# EEM_connector.net
KiCad netlist of a schematic drawn in Altium Designer
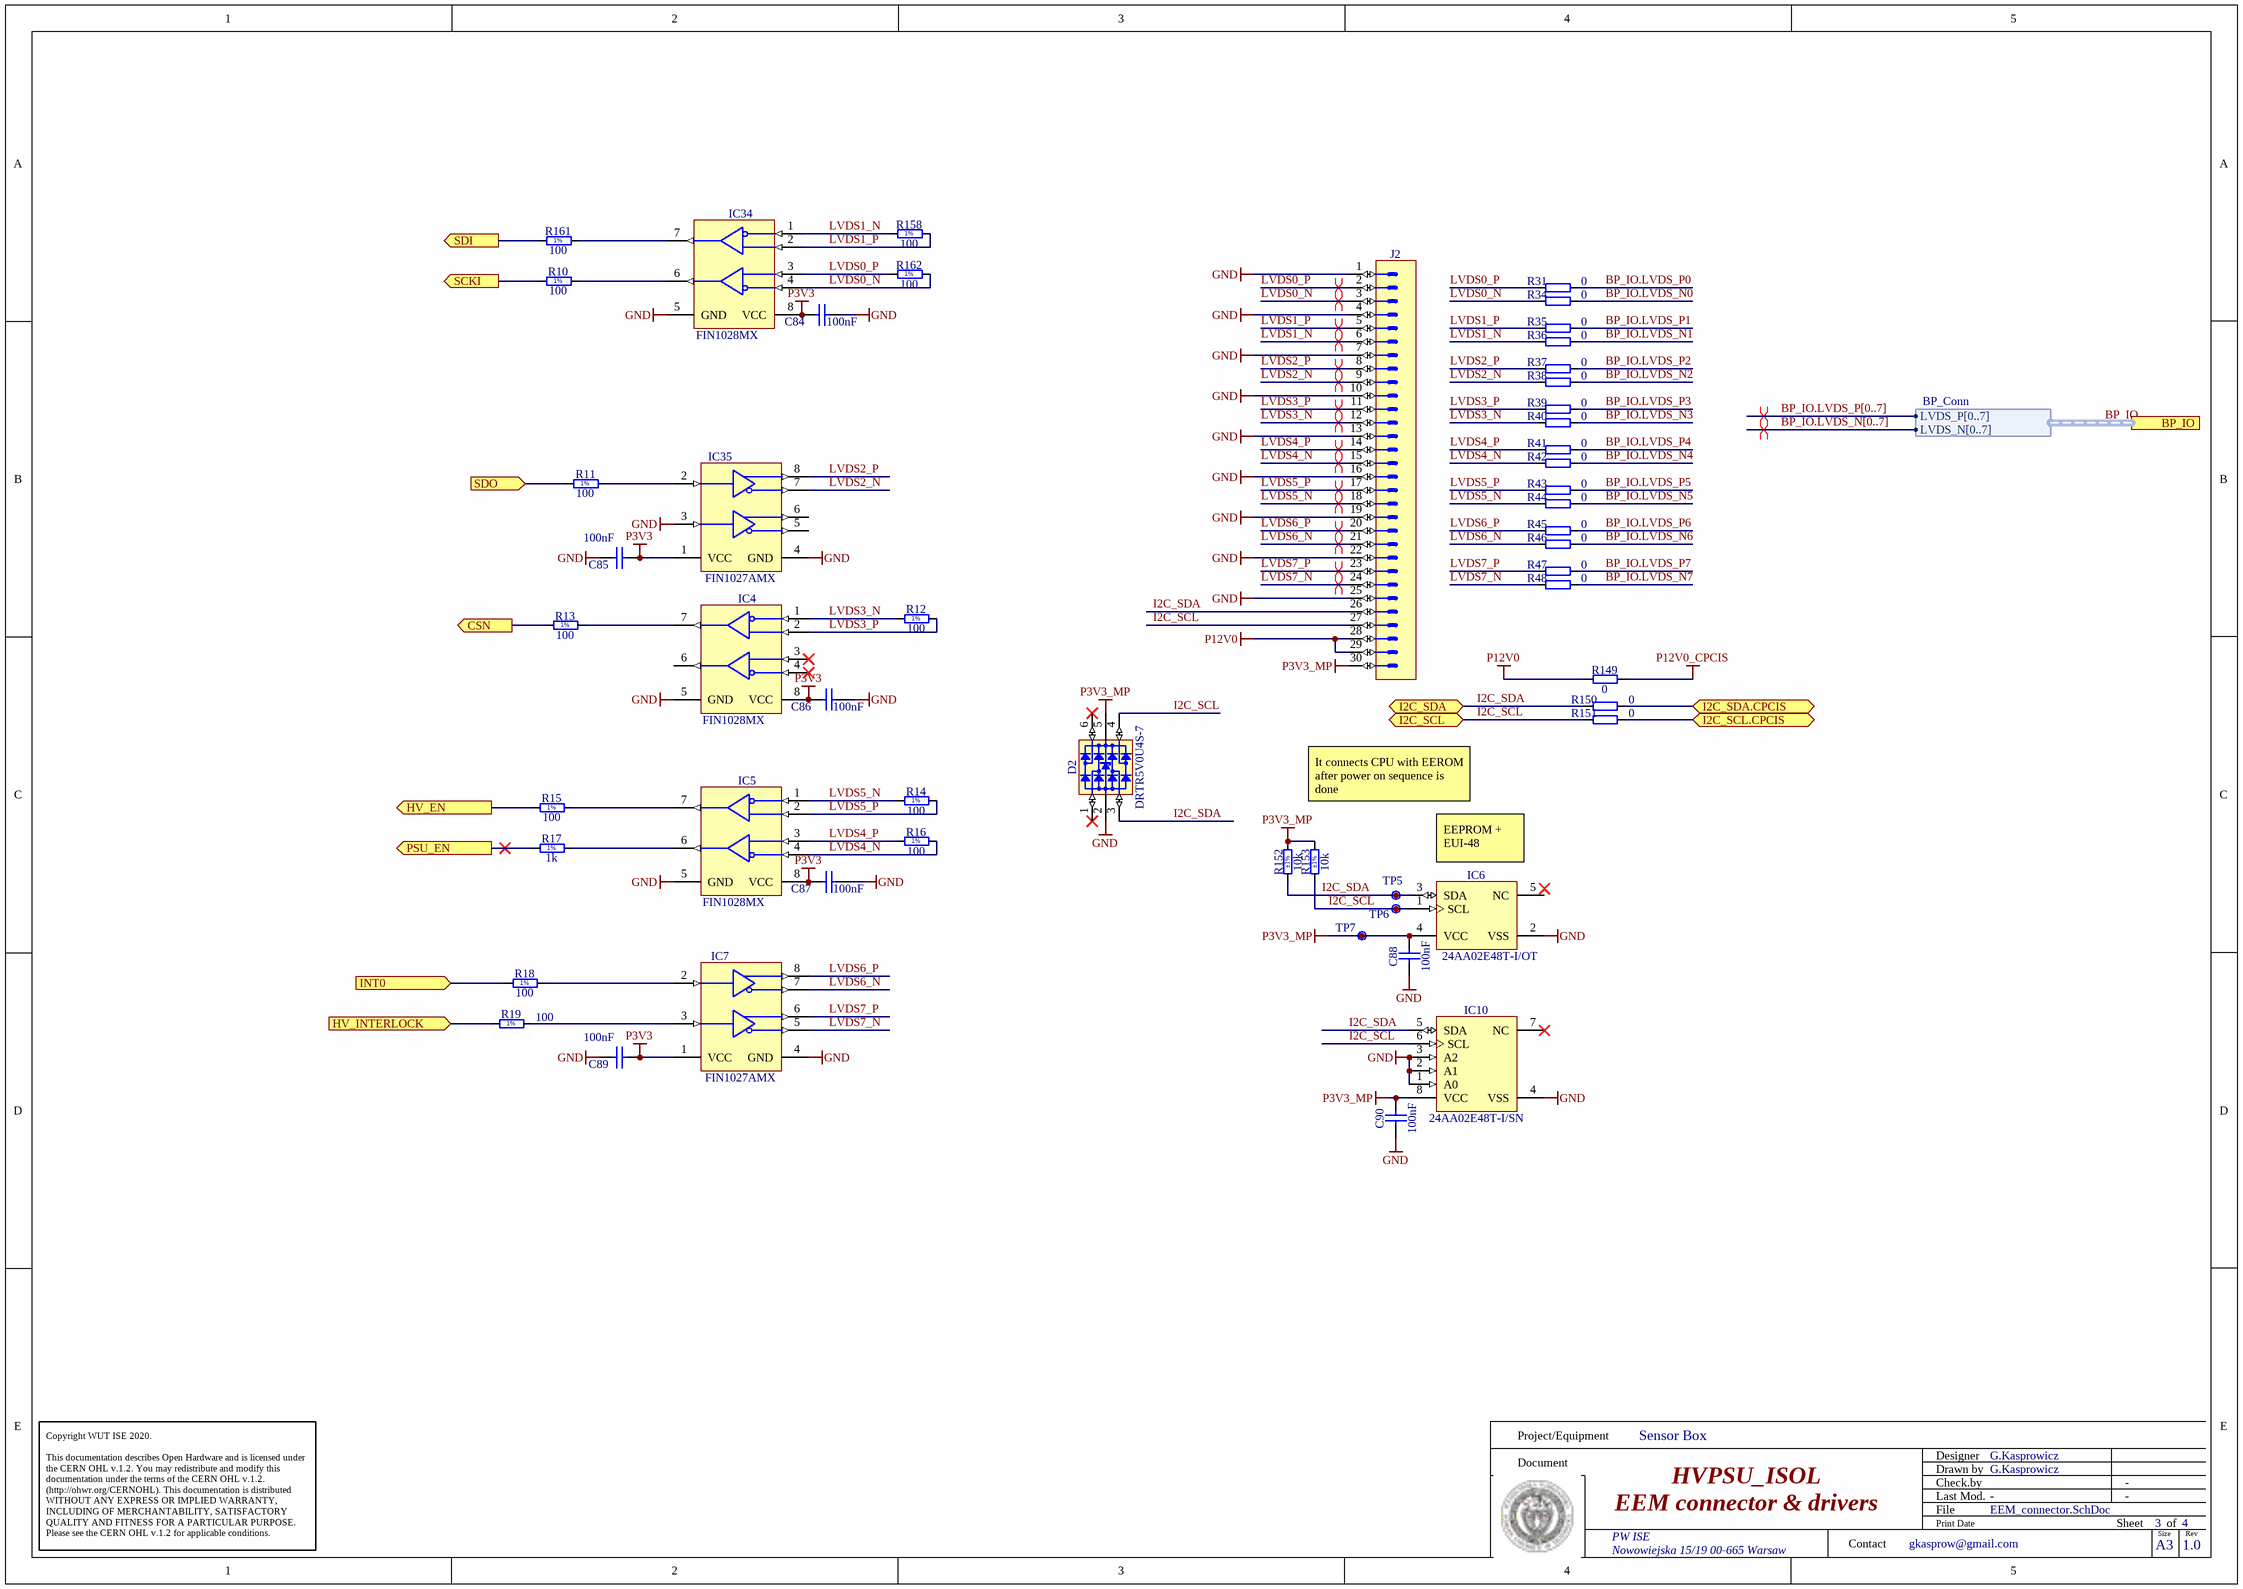
[diagram p0: EEM_connector.SchDoc]

(export (version "E")
  (design (tool "Eeschema 10.0.6"))
  (components
    (comp (ref "C84")
      (value "100nF")
      (footprint "CAPC1005X55N")
      (description "Non-polarised capacitor")
      (fields
        (field (name "PART NUMBER") "CC0402_100NF_16V_10%_X5R")
        (field (name "VOLTAGE") "16V")
        (field (name "AUTHOR") "CERN DEM JLC")
      )
      (libsource (lib "Capacitors") (part "Capacitor - non polarized"))
    )
    (comp (ref "C85")
      (value "100nF")
      (footprint "CAPC1005X55N")
      (description "Non-polarised capacitor")
      (fields
        (field (name "PART NUMBER") "CC0402_100NF_16V_10%_X5R")
        (field (name "VOLTAGE") "16V")
        (field (name "AUTHOR") "CERN DEM JLC")
      )
      (libsource (lib "Capacitors") (part "Capacitor - non polarized"))
    )
    (comp (ref "C86")
      (value "100nF")
      (footprint "CAPC1005X55N")
      (description "Non-polarised capacitor")
      (fields
        (field (name "PART NUMBER") "CC0402_100NF_16V_10%_X5R")
        (field (name "VOLTAGE") "16V")
        (field (name "AUTHOR") "CERN DEM JLC")
      )
      (libsource (lib "Capacitors") (part "Capacitor - non polarized"))
    )
    (comp (ref "C87")
      (value "100nF")
      (footprint "CAPC1005X55N")
      (description "Non-polarised capacitor")
      (fields
        (field (name "PART NUMBER") "CC0402_100NF_16V_10%_X5R")
        (field (name "VOLTAGE") "16V")
        (field (name "AUTHOR") "CERN DEM JLC")
      )
      (libsource (lib "Capacitors") (part "Capacitor - non polarized"))
    )
    (comp (ref "C88")
      (value "100nF")
      (footprint "CAPC1005X55N")
      (description "Non-polarised capacitor")
      (fields
        (field (name "PART NUMBER") "CC0402_100NF_16V_10%_X5R")
        (field (name "VOLTAGE") "16V")
        (field (name "AUTHOR") "CERN DEM JLC")
      )
      (libsource (lib "Capacitors") (part "Capacitor - non polarized"))
    )
    (comp (ref "C89")
      (value "100nF")
      (footprint "CAPC1005X55N")
      (description "Non-polarised capacitor")
      (fields
        (field (name "PART NUMBER") "CC0402_100NF_16V_10%_X5R")
        (field (name "VOLTAGE") "16V")
        (field (name "AUTHOR") "CERN DEM JLC")
      )
      (libsource (lib "Capacitors") (part "Capacitor - non polarized"))
    )
    (comp (ref "C90")
      (value "100nF")
      (footprint "CAPC1005X55N")
      (description "Non-polarised capacitor")
      (fields
        (field (name "PART NUMBER") "CC0402_100NF_16V_10%_X5R")
        (field (name "VOLTAGE") "16V")
        (field (name "AUTHOR") "CERN DEM JLC")
      )
      (libsource (lib "Capacitors") (part "Capacitor - non polarized"))
    )
    (comp (ref "D2")
      (value "DRTR5V0U4S-7")
      (footprint "SOT65P210X110-6N")
      (description "Integrated Quad Ultra-Low Capacitance ESD Protection")
      (fields (field (name "MANUFACTURER") "DIODES") (field (name "AUTHOR") "GK"))
      (libsource (lib "Diodes") (part "D_TVS_DRTR5V0U4S-7"))
    )
    (comp (ref "IC4")
      (value "FIN1028MX")
      (footprint "SOIC127P600X175-8N")
      (description "3.3V LVDS 2-Bit High-Speed Differential Reciever")
      (fields (field (name "MANUFACTURER") "ON Semiconductor") (field (name "AUTHOR") "GK"))
      (libsource (lib "LIBRARY_SCH") (part "IFC_FIN1028"))
    )
    (comp (ref "IC5")
      (value "FIN1028MX")
      (footprint "SOIC127P600X175-8N")
      (description "3.3V LVDS 2-Bit High-Speed Differential Reciever")
      (fields (field (name "MANUFACTURER") "ON Semiconductor") (field (name "AUTHOR") "GK"))
      (libsource (lib "LIBRARY_SCH") (part "IFC_FIN1028"))
    )
    (comp (ref "IC6")
      (value "24AA02E48T-I/OT")
      (footprint "SOT95P280X145-5N")
      (description "1.7V-5.5V, 2K I2C Serial EEPROM With EUI-48 Node Identity")
      (fields (field (name "MANUFACTURER") "MICROCHIP TECHNOLOGY") (field (name "AUTHOR") "CERN DEM MR"))
      (libsource (lib "ICs And Semiconductors") (part "24AA02E48T-I/OT"))
    )
    (comp (ref "IC7")
      (value "FIN1027AMX")
      (footprint "SOIC127P600X175-8N")
      (description "3.3V LVDS, 2-Bit, High-Speed, Differential Driver")
      (fields (field (name "MANUFACTURER") "ON Semiconductor") (field (name "AUTHOR") "GK"))
      (libsource (lib "LIBRARY_SCH") (part "IFC_FIN1027A"))
    )
    (comp (ref "IC10")
      (value "24AA02E48T-I/SN")
      (footprint "SOIC127P600X175-8N")
      (description "1.7V-5.5V, 2K I2C™ Serial EEPROMs with EUI-48™ Node Identity")
      (fields (field (name "MANUFACTURER") "MICROCHIP TECHNOLOGY") (field (name "AUTHOR") "CERN DEM MR"))
      (libsource (lib "ICs And Semiconductors") (part "24AA025E48-I/SN"))
    )
    (comp (ref "IC34")
      (value "FIN1028MX")
      (footprint "SOIC127P600X175-8N")
      (description "3.3V LVDS 2-Bit High-Speed Differential Reciever")
      (fields (field (name "MANUFACTURER") "ON Semiconductor") (field (name "AUTHOR") "GK"))
      (libsource (lib "LIBRARY_SCH") (part "IFC_FIN1028"))
    )
    (comp (ref "IC35")
      (value "FIN1027AMX")
      (footprint "SOIC127P600X175-8N")
      (description "3.3V LVDS, 2-Bit, High-Speed, Differential Driver")
      (fields (field (name "MANUFACTURER") "ON Semiconductor") (field (name "AUTHOR") "GK"))
      (libsource (lib "LIBRARY_SCH") (part "IFC_FIN1027A"))
    )
    (comp (ref "J2")
      (value "IDC")
      (footprint "3M_N2530-6002RB")
      (description "Connector 30 Male")
      (fields
        (field (name "PART NUMBER") "3M_N2530-6002RB")
        (field (name "MANUFACTURER") "3M")
        (field (name "AUTHOR") "CERN DEM JLC")
      )
      (libsource (lib "Connectors") (part "Connector 30 Male"))
    )
    (comp (ref "R10")
      (value "100")
      (footprint "RESC1005X40N")
      (description "Resistor - 1%")
      (fields
        (field (name "PART NUMBER") "R0402_100R_1%_0.0625W_100PPM")
        (field (name "POWER") "0.0625W")
        (field (name "AUTHOR") "CERN DEM JLC")
      )
      (libsource (lib "Resistors") (part "Resistor - 1%"))
    )
    (comp (ref "R11")
      (value "100")
      (footprint "RESC1005X40N")
      (description "Resistor - 1%")
      (fields
        (field (name "PART NUMBER") "R0402_100R_1%_0.0625W_100PPM")
        (field (name "POWER") "0.0625W")
        (field (name "AUTHOR") "CERN DEM JLC")
      )
      (libsource (lib "Resistors") (part "Resistor - 1%"))
    )
    (comp (ref "R12")
      (value "100")
      (footprint "RESC1005X40N")
      (description "Resistor - 1%")
      (fields
        (field (name "PART NUMBER") "R0402_100R_1%_0.0625W_100PPM")
        (field (name "POWER") "0.0625W")
        (field (name "AUTHOR") "CERN DEM JLC")
      )
      (libsource (lib "Resistors") (part "Resistor - 1%"))
    )
    (comp (ref "R13")
      (value "100")
      (footprint "RESC1005X40N")
      (description "Resistor - 1%")
      (fields
        (field (name "PART NUMBER") "R0402_100R_1%_0.0625W_100PPM")
        (field (name "POWER") "0.0625W")
        (field (name "AUTHOR") "CERN DEM JLC")
      )
      (libsource (lib "Resistors") (part "Resistor - 1%"))
    )
    (comp (ref "R14")
      (value "100")
      (footprint "RESC1005X40N")
      (description "Resistor - 1%")
      (fields
        (field (name "PART NUMBER") "R0402_100R_1%_0.0625W_100PPM")
        (field (name "POWER") "0.0625W")
        (field (name "AUTHOR") "CERN DEM JLC")
      )
      (libsource (lib "Resistors") (part "Resistor - 1%"))
    )
    (comp (ref "R15")
      (value "100")
      (footprint "RESC1005X40N")
      (description "Resistor - 1%")
      (fields
        (field (name "PART NUMBER") "R0402_100R_1%_0.0625W_100PPM")
        (field (name "POWER") "0.0625W")
        (field (name "AUTHOR") "CERN DEM JLC")
      )
      (libsource (lib "Resistors") (part "Resistor - 1%"))
    )
    (comp (ref "R16")
      (value "100")
      (footprint "RESC1005X40N")
      (description "Resistor - 1%")
      (fields
        (field (name "PART NUMBER") "R0402_100R_1%_0.0625W_100PPM")
        (field (name "POWER") "0.0625W")
        (field (name "AUTHOR") "CERN DEM JLC")
      )
      (libsource (lib "Resistors") (part "Resistor - 1%"))
    )
    (comp (ref "R17")
      (value "1k")
      (footprint "RESC1005X40N")
      (description "Resistor - 1%")
      (fields
        (field (name "PART NUMBER") "R0402_1K_1%_0.0625W_100PPM")
        (field (name "POWER") "0.0625W")
        (field (name "AUTHOR") "CERN DEM JLC")
      )
      (libsource (lib "Resistors") (part "Resistor - 1%"))
    )
    (comp (ref "R18")
      (value "100")
      (footprint "RESC1005X40N")
      (description "Resistor - 1%")
      (fields
        (field (name "PART NUMBER") "R0402_100R_1%_0.0625W_100PPM")
        (field (name "POWER") "0.0625W")
        (field (name "AUTHOR") "CERN DEM JLC")
      )
      (libsource (lib "Resistors") (part "Resistor - 1%"))
    )
    (comp (ref "R19")
      (value "100")
      (footprint "RESC1005X40N")
      (description "Resistor - 1%")
      (fields
        (field (name "PART NUMBER") "R0402_100R_1%_0.0625W_100PPM")
        (field (name "POWER") "0.0625W")
        (field (name "AUTHOR") "CERN DEM JLC")
      )
      (libsource (lib "Resistors") (part "Resistor - 1%"))
    )
    (comp (ref "R31")
      (value "0")
      (footprint "RESC1005X40N")
      (description "Resistor")
      (fields
        (field (name "PART NUMBER") "R0402_0R_JUMPER")
        (field (name "MANUFACTURER") "GENERIC")
        (field (name "AUTHOR") "CERN DEM JLC")
      )
      (libsource (lib "Resistors") (part "Resistor"))
    )
    (comp (ref "R34")
      (value "0")
      (footprint "RESC1005X40N")
      (description "Resistor")
      (fields
        (field (name "PART NUMBER") "R0402_0R_JUMPER")
        (field (name "MANUFACTURER") "GENERIC")
        (field (name "AUTHOR") "CERN DEM JLC")
      )
      (libsource (lib "Resistors") (part "Resistor"))
    )
    (comp (ref "R35")
      (value "0")
      (footprint "RESC1005X40N")
      (description "Resistor")
      (fields
        (field (name "PART NUMBER") "R0402_0R_JUMPER")
        (field (name "MANUFACTURER") "GENERIC")
        (field (name "AUTHOR") "CERN DEM JLC")
      )
      (libsource (lib "Resistors") (part "Resistor"))
    )
    (comp (ref "R36")
      (value "0")
      (footprint "RESC1005X40N")
      (description "Resistor")
      (fields
        (field (name "PART NUMBER") "R0402_0R_JUMPER")
        (field (name "MANUFACTURER") "GENERIC")
        (field (name "AUTHOR") "CERN DEM JLC")
      )
      (libsource (lib "Resistors") (part "Resistor"))
    )
    (comp (ref "R37")
      (value "0")
      (footprint "RESC1005X40N")
      (description "Resistor")
      (fields
        (field (name "PART NUMBER") "R0402_0R_JUMPER")
        (field (name "MANUFACTURER") "GENERIC")
        (field (name "AUTHOR") "CERN DEM JLC")
      )
      (libsource (lib "Resistors") (part "Resistor"))
    )
    (comp (ref "R38")
      (value "0")
      (footprint "RESC1005X40N")
      (description "Resistor")
      (fields
        (field (name "PART NUMBER") "R0402_0R_JUMPER")
        (field (name "MANUFACTURER") "GENERIC")
        (field (name "AUTHOR") "CERN DEM JLC")
      )
      (libsource (lib "Resistors") (part "Resistor"))
    )
    (comp (ref "R39")
      (value "0")
      (footprint "RESC1005X40N")
      (description "Resistor")
      (fields
        (field (name "PART NUMBER") "R0402_0R_JUMPER")
        (field (name "MANUFACTURER") "GENERIC")
        (field (name "AUTHOR") "CERN DEM JLC")
      )
      (libsource (lib "Resistors") (part "Resistor"))
    )
    (comp (ref "R40")
      (value "0")
      (footprint "RESC1005X40N")
      (description "Resistor")
      (fields
        (field (name "PART NUMBER") "R0402_0R_JUMPER")
        (field (name "MANUFACTURER") "GENERIC")
        (field (name "AUTHOR") "CERN DEM JLC")
      )
      (libsource (lib "Resistors") (part "Resistor"))
    )
    (comp (ref "R41")
      (value "0")
      (footprint "RESC1005X40N")
      (description "Resistor")
      (fields
        (field (name "PART NUMBER") "R0402_0R_JUMPER")
        (field (name "MANUFACTURER") "GENERIC")
        (field (name "AUTHOR") "CERN DEM JLC")
      )
      (libsource (lib "Resistors") (part "Resistor"))
    )
    (comp (ref "R42")
      (value "0")
      (footprint "RESC1005X40N")
      (description "Resistor")
      (fields
        (field (name "PART NUMBER") "R0402_0R_JUMPER")
        (field (name "MANUFACTURER") "GENERIC")
        (field (name "AUTHOR") "CERN DEM JLC")
      )
      (libsource (lib "Resistors") (part "Resistor"))
    )
    (comp (ref "R43")
      (value "0")
      (footprint "RESC1005X40N")
      (description "Resistor")
      (fields
        (field (name "PART NUMBER") "R0402_0R_JUMPER")
        (field (name "MANUFACTURER") "GENERIC")
        (field (name "AUTHOR") "CERN DEM JLC")
      )
      (libsource (lib "Resistors") (part "Resistor"))
    )
    (comp (ref "R44")
      (value "0")
      (footprint "RESC1005X40N")
      (description "Resistor")
      (fields
        (field (name "PART NUMBER") "R0402_0R_JUMPER")
        (field (name "MANUFACTURER") "GENERIC")
        (field (name "AUTHOR") "CERN DEM JLC")
      )
      (libsource (lib "Resistors") (part "Resistor"))
    )
    (comp (ref "R45")
      (value "0")
      (footprint "RESC1005X40N")
      (description "Resistor")
      (fields
        (field (name "PART NUMBER") "R0402_0R_JUMPER")
        (field (name "MANUFACTURER") "GENERIC")
        (field (name "AUTHOR") "CERN DEM JLC")
      )
      (libsource (lib "Resistors") (part "Resistor"))
    )
    (comp (ref "R46")
      (value "0")
      (footprint "RESC1005X40N")
      (description "Resistor")
      (fields
        (field (name "PART NUMBER") "R0402_0R_JUMPER")
        (field (name "MANUFACTURER") "GENERIC")
        (field (name "AUTHOR") "CERN DEM JLC")
      )
      (libsource (lib "Resistors") (part "Resistor"))
    )
    (comp (ref "R47")
      (value "0")
      (footprint "RESC1005X40N")
      (description "Resistor")
      (fields
        (field (name "PART NUMBER") "R0402_0R_JUMPER")
        (field (name "MANUFACTURER") "GENERIC")
        (field (name "AUTHOR") "CERN DEM JLC")
      )
      (libsource (lib "Resistors") (part "Resistor"))
    )
    (comp (ref "R48")
      (value "0")
      (footprint "RESC1005X40N")
      (description "Resistor")
      (fields
        (field (name "PART NUMBER") "R0402_0R_JUMPER")
        (field (name "MANUFACTURER") "GENERIC")
        (field (name "AUTHOR") "CERN DEM JLC")
      )
      (libsource (lib "Resistors") (part "Resistor"))
    )
    (comp (ref "R149")
      (value "0")
      (footprint "RESC2012X60N")
      (description "Resistor")
      (fields
        (field (name "PART NUMBER") "R0805_0R_JUMPER")
        (field (name "MANUFACTURER") "GENERIC")
        (field (name "AUTHOR") "CERN DEM JLC")
      )
      (libsource (lib "Resistors") (part "Resistor"))
    )
    (comp (ref "R150")
      (value "0")
      (footprint "RESC1005X40N")
      (description "Resistor")
      (fields
        (field (name "PART NUMBER") "R0402_0R_JUMPER")
        (field (name "MANUFACTURER") "GENERIC")
        (field (name "AUTHOR") "CERN DEM JLC")
      )
      (libsource (lib "Resistors") (part "Resistor"))
    )
    (comp (ref "R151")
      (value "0")
      (footprint "RESC1005X40N")
      (description "Resistor")
      (fields
        (field (name "PART NUMBER") "R0402_0R_JUMPER")
        (field (name "MANUFACTURER") "GENERIC")
        (field (name "AUTHOR") "CERN DEM JLC")
      )
      (libsource (lib "Resistors") (part "Resistor"))
    )
    (comp (ref "R152")
      (value "10k")
      (footprint "RESC1005X40N")
      (description "Resistor - 1%")
      (fields
        (field (name "TOLERANCE") "±1%")
        (field (name "PART NUMBER") "R0402_10K_1%_0.0625W_100PPM")
        (field (name "POWER") "0.0625W")
        (field (name "AUTHOR") "CERN DEM JLC")
      )
      (libsource (lib "Resistors") (part "Resistor - 1%"))
    )
    (comp (ref "R153")
      (value "10k")
      (footprint "RESC1005X40N")
      (description "Resistor - 1%")
      (fields
        (field (name "TOLERANCE") "±1%")
        (field (name "PART NUMBER") "R0402_10K_1%_0.0625W_100PPM")
        (field (name "POWER") "0.0625W")
        (field (name "AUTHOR") "CERN DEM JLC")
      )
      (libsource (lib "Resistors") (part "Resistor - 1%"))
    )
    (comp (ref "R158")
      (value "100")
      (footprint "RESC1005X40N")
      (description "Resistor - 1%")
      (fields
        (field (name "PART NUMBER") "R0402_100R_1%_0.0625W_100PPM")
        (field (name "POWER") "0.0625W")
        (field (name "AUTHOR") "CERN DEM JLC")
      )
      (libsource (lib "Resistors") (part "Resistor - 1%"))
    )
    (comp (ref "R161")
      (value "100")
      (footprint "RESC1005X40N")
      (description "Resistor - 1%")
      (fields
        (field (name "PART NUMBER") "R0402_100R_1%_0.0625W_100PPM")
        (field (name "POWER") "0.0625W")
        (field (name "AUTHOR") "CERN DEM JLC")
      )
      (libsource (lib "Resistors") (part "Resistor - 1%"))
    )
    (comp (ref "R162")
      (value "100")
      (footprint "RESC1005X40N")
      (description "Resistor - 1%")
      (fields
        (field (name "PART NUMBER") "R0402_100R_1%_0.0625W_100PPM")
        (field (name "POWER") "0.0625W")
        (field (name "AUTHOR") "CERN DEM JLC")
      )
      (libsource (lib "Resistors") (part "Resistor - 1%"))
    )
    (comp (ref "TP5")
      (value "Test Point")
      (footprint "TPS127")
      (fields (field (name "PART NUMBER") "SMD_PAD_1.27X1.27MM") (field (name "AUTHOR") "CERN DEM JLC"))
      (libsource (lib "Eletro-mechanical") (part "Test Point"))
    )
    (comp (ref "TP6")
      (value "Test Point")
      (footprint "TPS127")
      (fields (field (name "PART NUMBER") "SMD_PAD_1.27X1.27MM") (field (name "AUTHOR") "CERN DEM JLC"))
      (libsource (lib "Eletro-mechanical") (part "Test Point"))
    )
    (comp (ref "TP7")
      (value "Test Point")
      (footprint "TPS127")
      (fields (field (name "PART NUMBER") "SMD_PAD_1.27X1.27MM") (field (name "AUTHOR") "CERN DEM JLC"))
      (libsource (lib "Eletro-mechanical") (part "Test Point"))
    )
  )
  (nets
    (net (code "2") (name "/BP_IO.LVDS_N0") (class "Default")
      (node (ref "R34") (pin "2") (pinfunction "2_2") (pintype "passive"))
    )
    (net (code "3") (name "/BP_IO.LVDS_N1") (class "Default")
      (node (ref "R36") (pin "2") (pinfunction "2_2") (pintype "passive"))
    )
    (net (code "4") (name "/BP_IO.LVDS_N2") (class "Default")
      (node (ref "R38") (pin "2") (pinfunction "2_2") (pintype "passive"))
    )
    (net (code "5") (name "/BP_IO.LVDS_N3") (class "Default")
      (node (ref "R40") (pin "2") (pinfunction "2_2") (pintype "passive"))
    )
    (net (code "6") (name "/BP_IO.LVDS_N4") (class "Default")
      (node (ref "R42") (pin "2") (pinfunction "2_2") (pintype "passive"))
    )
    (net (code "7") (name "/BP_IO.LVDS_N5") (class "Default")
      (node (ref "R44") (pin "2") (pinfunction "2_2") (pintype "passive"))
    )
    (net (code "8") (name "/BP_IO.LVDS_N6") (class "Default")
      (node (ref "R46") (pin "2") (pinfunction "2_2") (pintype "passive"))
    )
    (net (code "9") (name "/BP_IO.LVDS_N7") (class "Default")
      (node (ref "R48") (pin "2") (pinfunction "2_2") (pintype "passive"))
    )
    (net (code "10") (name "/BP_IO.LVDS_P0") (class "Default")
      (node (ref "R31") (pin "2") (pinfunction "2_2") (pintype "passive"))
    )
    (net (code "11") (name "/BP_IO.LVDS_P1") (class "Default")
      (node (ref "R35") (pin "2") (pinfunction "2_2") (pintype "passive"))
    )
    (net (code "12") (name "/BP_IO.LVDS_P2") (class "Default")
      (node (ref "R37") (pin "2") (pinfunction "2_2") (pintype "passive"))
    )
    (net (code "13") (name "/BP_IO.LVDS_P3") (class "Default")
      (node (ref "R39") (pin "2") (pinfunction "2_2") (pintype "passive"))
    )
    (net (code "14") (name "/BP_IO.LVDS_P4") (class "Default")
      (node (ref "R41") (pin "2") (pinfunction "2_2") (pintype "passive"))
    )
    (net (code "15") (name "/BP_IO.LVDS_P5") (class "Default")
      (node (ref "R43") (pin "2") (pinfunction "2_2") (pintype "passive"))
    )
    (net (code "16") (name "/BP_IO.LVDS_P6") (class "Default")
      (node (ref "R45") (pin "2") (pinfunction "2_2") (pintype "passive"))
    )
    (net (code "17") (name "/BP_IO.LVDS_P7") (class "Default")
      (node (ref "R47") (pin "2") (pinfunction "2_2") (pintype "passive"))
    )
    (net (code "19") (name "/CSN") (class "Default")
      (node (ref "R13") (pin "1") (pinfunction "1_1") (pintype "passive"))
    )
    (net (code "20") (name "/HV_EN") (class "Default")
      (node (ref "R15") (pin "1") (pinfunction "1_1") (pintype "passive"))
    )
    (net (code "21") (name "/HV_INTERLOCK") (class "Default")
      (node (ref "R19") (pin "1") (pinfunction "1_1") (pintype "passive"))
    )
    (net (code "22") (name "/I2C_SCL") (class "Default")
      (node (ref "D2") (pin "4") (pinfunction "I/O3_4") (pintype "bidirectional"))
      (node (ref "IC10") (pin "6") (pinfunction "SCL_6") (pintype "input"))
      (node (ref "IC6") (pin "1") (pinfunction "SCL_1") (pintype "input"))
      (node (ref "J2") (pin "27") (pinfunction "27_27") (pintype "bidirectional"))
      (node (ref "R151") (pin "1") (pinfunction "1_1") (pintype "passive"))
      (node (ref "R153") (pin "1") (pinfunction "1_1") (pintype "passive"))
      (node (ref "TP6") (pin "1") (pinfunction "1_1") (pintype "bidirectional"))
    )
    (net (code "23") (name "/I2C_SCL.CPCIS") (class "Default")
      (node (ref "R151") (pin "2") (pinfunction "2_2") (pintype "passive"))
    )
    (net (code "24") (name "/I2C_SDA") (class "Default")
      (node (ref "D2") (pin "3") (pinfunction "I/O2_3") (pintype "bidirectional"))
      (node (ref "IC10") (pin "5") (pinfunction "SDA_5") (pintype "bidirectional"))
      (node (ref "IC6") (pin "3") (pinfunction "SDA_3") (pintype "bidirectional"))
      (node (ref "J2") (pin "26") (pinfunction "26_26") (pintype "bidirectional"))
      (node (ref "R150") (pin "1") (pinfunction "1_1") (pintype "passive"))
      (node (ref "R152") (pin "1") (pinfunction "1_1") (pintype "passive"))
      (node (ref "TP5") (pin "1") (pinfunction "1_1") (pintype "bidirectional"))
    )
    (net (code "25") (name "/I2C_SDA.CPCIS") (class "Default")
      (node (ref "R150") (pin "2") (pinfunction "2_2") (pintype "passive"))
    )
    (net (code "26") (name "/INT0") (class "Default")
      (node (ref "R18") (pin "1") (pinfunction "1_1") (pintype "passive"))
    )
    (net (code "27") (name "/LVDS0_N") (class "Default")
      (node (ref "IC34") (pin "4") (pinfunction "RIN2-_4") (pintype "input"))
      (node (ref "J2") (pin "3") (pinfunction "3_3") (pintype "bidirectional"))
      (node (ref "R162") (pin "2") (pinfunction "2_2") (pintype "passive"))
      (node (ref "R34") (pin "1") (pinfunction "1_1") (pintype "passive"))
    )
    (net (code "28") (name "/LVDS0_P") (class "Default")
      (node (ref "IC34") (pin "3") (pinfunction "RIN2+_3") (pintype "input"))
      (node (ref "J2") (pin "2") (pinfunction "2_2") (pintype "bidirectional"))
      (node (ref "R162") (pin "1") (pinfunction "1_1") (pintype "passive"))
      (node (ref "R31") (pin "1") (pinfunction "1_1") (pintype "passive"))
    )
    (net (code "29") (name "/LVDS1_N") (class "Default")
      (node (ref "IC34") (pin "1") (pinfunction "RIN1-_1") (pintype "input"))
      (node (ref "J2") (pin "6") (pinfunction "6_6") (pintype "bidirectional"))
      (node (ref "R158") (pin "1") (pinfunction "1_1") (pintype "passive"))
      (node (ref "R36") (pin "1") (pinfunction "1_1") (pintype "passive"))
    )
    (net (code "30") (name "/LVDS1_P") (class "Default")
      (node (ref "IC34") (pin "2") (pinfunction "RIN1+_2") (pintype "input"))
      (node (ref "J2") (pin "5") (pinfunction "5_5") (pintype "bidirectional"))
      (node (ref "R158") (pin "2") (pinfunction "2_2") (pintype "passive"))
      (node (ref "R35") (pin "1") (pinfunction "1_1") (pintype "passive"))
    )
    (net (code "31") (name "/LVDS2_N") (class "Default")
      (node (ref "IC35") (pin "7") (pinfunction "DOUT-_7") (pintype "output"))
      (node (ref "J2") (pin "9") (pinfunction "9_9") (pintype "bidirectional"))
      (node (ref "R38") (pin "1") (pinfunction "1_1") (pintype "passive"))
    )
    (net (code "32") (name "/LVDS2_P") (class "Default")
      (node (ref "IC35") (pin "8") (pinfunction "DOUT+_8") (pintype "output"))
      (node (ref "J2") (pin "8") (pinfunction "8_8") (pintype "bidirectional"))
      (node (ref "R37") (pin "1") (pinfunction "1_1") (pintype "passive"))
    )
    (net (code "33") (name "/LVDS3_N") (class "Default")
      (node (ref "IC4") (pin "1") (pinfunction "RIN1-_1") (pintype "input"))
      (node (ref "J2") (pin "12") (pinfunction "12_12") (pintype "bidirectional"))
      (node (ref "R12") (pin "1") (pinfunction "1_1") (pintype "passive"))
      (node (ref "R40") (pin "1") (pinfunction "1_1") (pintype "passive"))
    )
    (net (code "34") (name "/LVDS3_P") (class "Default")
      (node (ref "IC4") (pin "2") (pinfunction "RIN1+_2") (pintype "input"))
      (node (ref "J2") (pin "11") (pinfunction "11_11") (pintype "bidirectional"))
      (node (ref "R12") (pin "2") (pinfunction "2_2") (pintype "passive"))
      (node (ref "R39") (pin "1") (pinfunction "1_1") (pintype "passive"))
    )
    (net (code "35") (name "/LVDS4_N") (class "Default")
      (node (ref "IC5") (pin "4") (pinfunction "RIN2-_4") (pintype "input"))
      (node (ref "J2") (pin "15") (pinfunction "15_15") (pintype "bidirectional"))
      (node (ref "R16") (pin "2") (pinfunction "2_2") (pintype "passive"))
      (node (ref "R42") (pin "1") (pinfunction "1_1") (pintype "passive"))
    )
    (net (code "36") (name "/LVDS4_P") (class "Default")
      (node (ref "IC5") (pin "3") (pinfunction "RIN2+_3") (pintype "input"))
      (node (ref "J2") (pin "14") (pinfunction "14_14") (pintype "bidirectional"))
      (node (ref "R16") (pin "1") (pinfunction "1_1") (pintype "passive"))
      (node (ref "R41") (pin "1") (pinfunction "1_1") (pintype "passive"))
    )
    (net (code "37") (name "/LVDS5_N") (class "Default")
      (node (ref "IC5") (pin "1") (pinfunction "RIN1-_1") (pintype "input"))
      (node (ref "J2") (pin "18") (pinfunction "18_18") (pintype "bidirectional"))
      (node (ref "R14") (pin "1") (pinfunction "1_1") (pintype "passive"))
      (node (ref "R44") (pin "1") (pinfunction "1_1") (pintype "passive"))
    )
    (net (code "38") (name "/LVDS5_P") (class "Default")
      (node (ref "IC5") (pin "2") (pinfunction "RIN1+_2") (pintype "input"))
      (node (ref "J2") (pin "17") (pinfunction "17_17") (pintype "bidirectional"))
      (node (ref "R14") (pin "2") (pinfunction "2_2") (pintype "passive"))
      (node (ref "R43") (pin "1") (pinfunction "1_1") (pintype "passive"))
    )
    (net (code "39") (name "/LVDS6_N") (class "Default")
      (node (ref "IC7") (pin "7") (pinfunction "DOUT-_7") (pintype "output"))
      (node (ref "J2") (pin "21") (pinfunction "21_21") (pintype "bidirectional"))
      (node (ref "R46") (pin "1") (pinfunction "1_1") (pintype "passive"))
    )
    (net (code "40") (name "/LVDS6_P") (class "Default")
      (node (ref "IC7") (pin "8") (pinfunction "DOUT+_8") (pintype "output"))
      (node (ref "J2") (pin "20") (pinfunction "20_20") (pintype "bidirectional"))
      (node (ref "R45") (pin "1") (pinfunction "1_1") (pintype "passive"))
    )
    (net (code "41") (name "/LVDS7_N") (class "Default")
      (node (ref "IC7") (pin "5") (pinfunction "DOUT-_5") (pintype "output"))
      (node (ref "J2") (pin "24") (pinfunction "24_24") (pintype "bidirectional"))
      (node (ref "R48") (pin "1") (pinfunction "1_1") (pintype "passive"))
    )
    (net (code "42") (name "/LVDS7_P") (class "Default")
      (node (ref "IC7") (pin "6") (pinfunction "DOUT+_6") (pintype "output"))
      (node (ref "J2") (pin "23") (pinfunction "23_23") (pintype "bidirectional"))
      (node (ref "R47") (pin "1") (pinfunction "1_1") (pintype "passive"))
    )
    (net (code "43") (name "/PSU_EN") (class "Default")
      (node (ref "R17") (pin "1") (pinfunction "1_1") (pintype "passive"))
    )
    (net (code "44") (name "/SCKI") (class "Default")
      (node (ref "R10") (pin "1") (pinfunction "1_1") (pintype "passive"))
    )
    (net (code "45") (name "/SDI") (class "Default")
      (node (ref "R161") (pin "1") (pinfunction "1_1") (pintype "passive"))
    )
    (net (code "46") (name "/SDO") (class "Default")
      (node (ref "R11") (pin "1") (pinfunction "1_1") (pintype "passive"))
    )
    (net (code "48") (name "GND") (class "Default")
      (node (ref "C84") (pin "1") (pinfunction "1_1") (pintype "passive"))
      (node (ref "C85") (pin "1") (pinfunction "1_1") (pintype "passive"))
      (node (ref "C86") (pin "1") (pinfunction "1_1") (pintype "passive"))
      (node (ref "C87") (pin "1") (pinfunction "1_1") (pintype "passive"))
      (node (ref "C88") (pin "1") (pinfunction "1_1") (pintype "passive"))
      (node (ref "C89") (pin "1") (pinfunction "1_1") (pintype "passive"))
      (node (ref "C90") (pin "1") (pinfunction "1_1") (pintype "passive"))
      (node (ref "D2") (pin "2") (pinfunction "GND_2") (pintype "power_in"))
      (node (ref "IC10") (pin "1") (pinfunction "A0_1") (pintype "input"))
      (node (ref "IC10") (pin "2") (pinfunction "A1_2") (pintype "input"))
      (node (ref "IC10") (pin "3") (pinfunction "A2_3") (pintype "input"))
      (node (ref "IC10") (pin "4") (pinfunction "VSS_4") (pintype "power_in"))
      (node (ref "IC34") (pin "5") (pinfunction "GND_5") (pintype "power_in"))
      (node (ref "IC35") (pin "3") (pinfunction "DIN2RIN-_3") (pintype "input"))
      (node (ref "IC35") (pin "4") (pinfunction "GND_4") (pintype "power_in"))
      (node (ref "IC4") (pin "5") (pinfunction "GND_5") (pintype "power_in"))
      (node (ref "IC5") (pin "5") (pinfunction "GND_5") (pintype "power_in"))
      (node (ref "IC6") (pin "2") (pinfunction "VSS_2") (pintype "power_in"))
      (node (ref "IC7") (pin "4") (pinfunction "GND_4") (pintype "power_in"))
      (node (ref "J2") (pin "1") (pinfunction "1_1") (pintype "bidirectional"))
      (node (ref "J2") (pin "10") (pinfunction "10_10") (pintype "bidirectional"))
      (node (ref "J2") (pin "13") (pinfunction "13_13") (pintype "bidirectional"))
      (node (ref "J2") (pin "16") (pinfunction "16_16") (pintype "bidirectional"))
      (node (ref "J2") (pin "19") (pinfunction "19_19") (pintype "bidirectional"))
      (node (ref "J2") (pin "22") (pinfunction "22_22") (pintype "bidirectional"))
      (node (ref "J2") (pin "25") (pinfunction "25_25") (pintype "bidirectional"))
      (node (ref "J2") (pin "4") (pinfunction "4_4") (pintype "bidirectional"))
      (node (ref "J2") (pin "7") (pinfunction "7_7") (pintype "bidirectional"))
    )
    (net (code "49") (name "Net-(IC4-ROUT1)") (class "Default")
      (node (ref "IC4") (pin "7") (pinfunction "ROUT1_7") (pintype "output"))
      (node (ref "R13") (pin "2") (pinfunction "2_2") (pintype "passive"))
    )
    (net (code "50") (name "Net-(IC5-ROUT1)") (class "Default")
      (node (ref "IC5") (pin "7") (pinfunction "ROUT1_7") (pintype "output"))
      (node (ref "R15") (pin "2") (pinfunction "2_2") (pintype "passive"))
    )
    (net (code "51") (name "Net-(IC5-ROUT2)") (class "Default")
      (node (ref "IC5") (pin "6") (pinfunction "ROUT2_6") (pintype "output"))
      (node (ref "R17") (pin "2") (pinfunction "2_2") (pintype "passive"))
    )
    (net (code "52") (name "Net-(IC7-DIN1)") (class "Default")
      (node (ref "IC7") (pin "2") (pinfunction "DIN1_2") (pintype "input"))
      (node (ref "R18") (pin "2") (pinfunction "2_2") (pintype "passive"))
    )
    (net (code "53") (name "Net-(IC7-DIN2RIN-)") (class "Default")
      (node (ref "IC7") (pin "3") (pinfunction "DIN2RIN-_3") (pintype "input"))
      (node (ref "R19") (pin "2") (pinfunction "2_2") (pintype "passive"))
    )
    (net (code "54") (name "Net-(IC34-ROUT1)") (class "Default")
      (node (ref "IC34") (pin "7") (pinfunction "ROUT1_7") (pintype "output"))
      (node (ref "R161") (pin "2") (pinfunction "2_2") (pintype "passive"))
    )
    (net (code "55") (name "Net-(IC34-ROUT2)") (class "Default")
      (node (ref "IC34") (pin "6") (pinfunction "ROUT2_6") (pintype "output"))
      (node (ref "R10") (pin "2") (pinfunction "2_2") (pintype "passive"))
    )
    (net (code "56") (name "Net-(IC35-DIN1)") (class "Default")
      (node (ref "IC35") (pin "2") (pinfunction "DIN1_2") (pintype "input"))
      (node (ref "R11") (pin "2") (pinfunction "2_2") (pintype "passive"))
    )
    (net (code "57") (name "P3V3") (class "Default")
      (node (ref "C84") (pin "2") (pinfunction "2_2") (pintype "passive"))
      (node (ref "C85") (pin "2") (pinfunction "2_2") (pintype "passive"))
      (node (ref "C86") (pin "2") (pinfunction "2_2") (pintype "passive"))
      (node (ref "C87") (pin "2") (pinfunction "2_2") (pintype "passive"))
      (node (ref "C89") (pin "2") (pinfunction "2_2") (pintype "passive"))
      (node (ref "IC34") (pin "8") (pinfunction "VCC_8") (pintype "power_in"))
      (node (ref "IC35") (pin "1") (pinfunction "VCC_1") (pintype "power_in"))
      (node (ref "IC4") (pin "8") (pinfunction "VCC_8") (pintype "power_in"))
      (node (ref "IC5") (pin "8") (pinfunction "VCC_8") (pintype "power_in"))
      (node (ref "IC7") (pin "1") (pinfunction "VCC_1") (pintype "power_in"))
    )
    (net (code "58") (name "P3V3_MP") (class "Default")
      (node (ref "C88") (pin "2") (pinfunction "2_2") (pintype "passive"))
      (node (ref "C90") (pin "2") (pinfunction "2_2") (pintype "passive"))
      (node (ref "D2") (pin "5") (pinfunction "VBUS_5") (pintype "power_in"))
      (node (ref "IC10") (pin "8") (pinfunction "VCC_8") (pintype "power_in"))
      (node (ref "IC6") (pin "4") (pinfunction "VCC_4") (pintype "power_in"))
      (node (ref "J2") (pin "30") (pinfunction "30_30") (pintype "bidirectional"))
      (node (ref "R152") (pin "2") (pinfunction "2_2") (pintype "passive"))
      (node (ref "R153") (pin "2") (pinfunction "2_2") (pintype "passive"))
      (node (ref "TP7") (pin "1") (pinfunction "1_1") (pintype "bidirectional"))
    )
    (net (code "59") (name "P12V0") (class "Default")
      (node (ref "J2") (pin "28") (pinfunction "28_28") (pintype "bidirectional"))
      (node (ref "J2") (pin "29") (pinfunction "29_29") (pintype "bidirectional"))
      (node (ref "R149") (pin "1") (pinfunction "1_1") (pintype "passive"))
    )
    (net (code "60") (name "P12V0_CPCIS") (class "Default")
      (node (ref "R149") (pin "2") (pinfunction "2_2") (pintype "passive"))
    )
    (net (code "61") (name "unconnected-(D2-I{slash}O1-Pad1)") (class "Default")
      (node (ref "D2") (pin "1") (pinfunction "I/O1_1") (pintype "bidirectional+no_connect"))
    )
    (net (code "62") (name "unconnected-(D2-I{slash}O4-Pad6)") (class "Default")
      (node (ref "D2") (pin "6") (pinfunction "I/O4_6") (pintype "bidirectional+no_connect"))
    )
    (net (code "63") (name "unconnected-(IC4-RIN2+-Pad3)") (class "Default")
      (node (ref "IC4") (pin "3") (pinfunction "RIN2+_3") (pintype "input+no_connect"))
    )
    (net (code "64") (name "unconnected-(IC4-RIN2--Pad4)") (class "Default")
      (node (ref "IC4") (pin "4") (pinfunction "RIN2-_4") (pintype "input+no_connect"))
    )
    (net (code "65") (name "unconnected-(IC4-ROUT2-Pad6)") (class "Default")
      (node (ref "IC4") (pin "6") (pinfunction "ROUT2_6") (pintype "output"))
    )
    (net (code "66") (name "unconnected-(IC6-NC-Pad5)") (class "Default")
      (node (ref "IC6") (pin "5") (pinfunction "NC_5") (pintype "passive"))
    )
    (net (code "67") (name "unconnected-(IC10-NC-Pad7)") (class "Default")
      (node (ref "IC10") (pin "7") (pinfunction "NC_7") (pintype "passive+no_connect"))
    )
    (net (code "68") (name "unconnected-(IC35-DOUT+-Pad6)") (class "Default")
      (node (ref "IC35") (pin "6") (pinfunction "DOUT+_6") (pintype "output"))
    )
    (net (code "69") (name "unconnected-(IC35-DOUT--Pad5)") (class "Default")
      (node (ref "IC35") (pin "5") (pinfunction "DOUT-_5") (pintype "output"))
    )
  )
)
